# Extension.net
KiCad netlist of a schematic drawn in Altium Designer
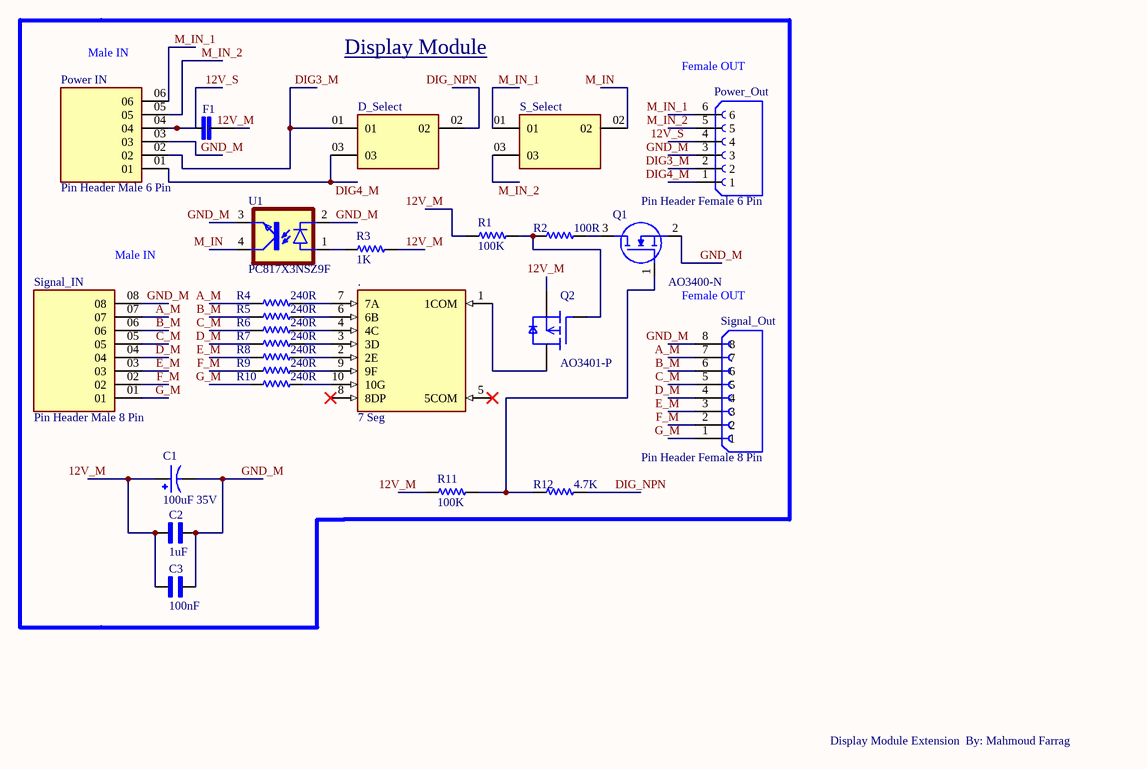
[diagram p0: Extension.SchDoc]

(export (version "E")
  (design (tool "Eeschema 10.0.6"))
  (components
    (comp (ref ".") (value "7 Seg") (footprint "2.3_7-SEG_DIS") (libsource (lib "Modules") (part "7 Seg")))
    (comp (ref "C1")
      (value "100uF 35V")
      (footprint "100uF 35V")
      (description "100ÂµF 35V Aluminum Electrolytic Capacitors Radial, Can - SMD 2000 Hrs @ 85Â°C")
      (fields (field (name "MP") "EEE-1VA101P") (field (name "MF") "Panasonic Electronic"))
      (libsource (lib "Capacitors") (part "100uF 35V"))
    )
    (comp (ref "C2")
      (value "1uF")
      (footprint "Capacitor 0805")
      (description "0.1 ÂµF Â±10% 50V Ceramic Capacitor X7R 0805 (2012 Metric)")
      (fields (field (name "MF") "Murata") (field (name "MP") "GCE21BR71H104KA01L"))
      (libsource (lib "Capacitors") (part "Capacitor 0805"))
    )
    (comp (ref "C3")
      (value "100nF")
      (footprint "Capacitor 0805")
      (description "0.1 ÂµF Â±10% 50V Ceramic Capacitor X7R 0805 (2012 Metric)")
      (fields (field (name "MF") "Murata") (field (name "MP") "GCE21BR71H104KA01L"))
      (libsource (lib "Capacitors") (part "Capacitor 0805"))
    )
    (comp (ref "D_Select")
      (value "Pin Header Male 3 Pin")
      (footprint "3Pin-M-Header_3MX1-254MM")
      (fields (field (name "MP") "TSW-101-23-L-T"))
      (libsource (lib "Connectors") (part "Pin Header Male 3 Pin"))
    )
    (comp (ref "F1")
      (value "Ferrite Bead 0805")
      (footprint "Ferrite Bead 0805")
      (description "BLM Series 0805 1 kOhm 200 mA 0.45 DCR Surface Mount Ferrite Bead")
      (fields (field (name "MF") "Murata") (field (name "MP") "BLM21AH102SN1D"))
      (libsource (lib "Resistors") (part "Ferrite Bead 0805"))
    )
    (comp (ref "Power IN")
      (value "Pin Header Male 6 Pin")
      (footprint "6Pin-M-Header_6MX1-254MM")
      (fields (field (name "MP") "MTSW-106-24-G-S-300"))
      (libsource (lib "Connectors") (part "Pin Header Male 6 Pin"))
    )
    (comp (ref "Power_Out")
      (value "Pin Header Female 6 Pin")
      (footprint "6Pin-F-Header_6FX1-254MM")
      (description "6 Position Total Single Row 2.54 mm Pitch Straight Female Header")
      (fields (field (name "MF") "Sullins Connector Solutions") (field (name "MP") "PPTC061LFBNRC"))
      (libsource (lib "Connectors") (part "Pin Header Female 6 Pin"))
    )
    (comp (ref "Q1")
      (value "AO3400-N")
      (footprint "AO-3400-N-SOT95")
      (description "N-Channel 30 V 5.8A (Ta) 1.4W (Ta) Surface Mount SOT-23-3")
      (fields (field (name "MF") "Alpha &") (field (name "MP") "AO3400"))
      (libsource (lib "ICs") (part "AO3400-N"))
    )
    (comp (ref "Q2")
      (value "AO3401-P")
      (footprint "AO-3401-P-SOT23-3")
      (description "P-Channel 30 V 4A (Ta) 1.4W (Ta) Surface Mount SOT-23-3")
      (fields (field (name "MF") "Alpha & Omega Semiconductor") (field (name "MP") "AO3401"))
      (libsource (lib "ICs") (part "AO3401-P"))
    )
    (comp (ref "R1")
      (value "100K")
      (footprint "Resistor 1206")
      (description "Fixed Resistor CRGCQ 1206 10K 5%")
      (fields (field (name "MF") "TE Connectivity") (field (name "MP") "CRGCQ1206J10K"))
      (libsource (lib "Resistors") (part "Resistor 1206"))
    )
    (comp (ref "R2")
      (value "100R")
      (footprint "Resistor 1206")
      (description "Fixed Resistor CRGCQ 1206 10K 5%")
      (fields (field (name "MF") "TE Connectivity") (field (name "MP") "CRGCQ1206J10K"))
      (libsource (lib "Resistors") (part "Resistor 1206"))
    )
    (comp (ref "R3")
      (value "1K")
      (footprint "Resistor 1206")
      (description "Fixed Resistor CRGCQ 1206 10K 5%")
      (fields (field (name "MF") "TE Connectivity") (field (name "MP") "CRGCQ1206J10K"))
      (libsource (lib "Resistors") (part "Resistor 1206"))
    )
    (comp (ref "R4")
      (value "240R")
      (footprint "Resistor 1206")
      (description "Fixed Resistor CRGCQ 1206 10K 5%")
      (fields (field (name "MF") "TE Connectivity") (field (name "MP") "CRGCQ1206J10K"))
      (libsource (lib "Resistors") (part "Resistor 1206"))
    )
    (comp (ref "R5")
      (value "240R")
      (footprint "Resistor 1206")
      (description "Fixed Resistor CRGCQ 1206 10K 5%")
      (fields (field (name "MF") "TE Connectivity") (field (name "MP") "CRGCQ1206J10K"))
      (libsource (lib "Resistors") (part "Resistor 1206"))
    )
    (comp (ref "R6")
      (value "240R")
      (footprint "Resistor 1206")
      (description "Fixed Resistor CRGCQ 1206 10K 5%")
      (fields (field (name "MF") "TE Connectivity") (field (name "MP") "CRGCQ1206J10K"))
      (libsource (lib "Resistors") (part "Resistor 1206"))
    )
    (comp (ref "R7")
      (value "240R")
      (footprint "Resistor 1206")
      (description "Fixed Resistor CRGCQ 1206 10K 5%")
      (fields (field (name "MF") "TE Connectivity") (field (name "MP") "CRGCQ1206J10K"))
      (libsource (lib "Resistors") (part "Resistor 1206"))
    )
    (comp (ref "R8")
      (value "240R")
      (footprint "Resistor 1206")
      (description "Fixed Resistor CRGCQ 1206 10K 5%")
      (fields (field (name "MF") "TE Connectivity") (field (name "MP") "CRGCQ1206J10K"))
      (libsource (lib "Resistors") (part "Resistor 1206"))
    )
    (comp (ref "R9")
      (value "240R")
      (footprint "Resistor 1206")
      (description "Fixed Resistor CRGCQ 1206 10K 5%")
      (fields (field (name "MF") "TE Connectivity") (field (name "MP") "CRGCQ1206J10K"))
      (libsource (lib "Resistors") (part "Resistor 1206"))
    )
    (comp (ref "R10")
      (value "240R")
      (footprint "Resistor 1206")
      (description "Fixed Resistor CRGCQ 1206 10K 5%")
      (fields (field (name "MF") "TE Connectivity") (field (name "MP") "CRGCQ1206J10K"))
      (libsource (lib "Resistors") (part "Resistor 1206"))
    )
    (comp (ref "R11")
      (value "100K")
      (footprint "Resistor 1206")
      (description "Fixed Resistor CRGCQ 1206 10K 5%")
      (fields (field (name "MF") "TE Connectivity") (field (name "MP") "CRGCQ1206J10K"))
      (libsource (lib "Resistors") (part "Resistor 1206"))
    )
    (comp (ref "R12")
      (value "4.7K")
      (footprint "Resistor 1206")
      (description "Fixed Resistor CRGCQ 1206 10K 5%")
      (fields (field (name "MF") "TE Connectivity") (field (name "MP") "CRGCQ1206J10K"))
      (libsource (lib "Resistors") (part "Resistor 1206"))
    )
    (comp (ref "Signal_IN")
      (value "Pin Header Male 8 Pin")
      (footprint "8Pin-M-Header_8MX1-254MM")
      (fields (field (name "MP") "HTSW-108-07-G-S-LL"))
      (libsource (lib "Connectors") (part "Pin Header Male 8 Pin"))
    )
    (comp (ref "Signal_Out")
      (value "Pin Header Female 8 Pin")
      (footprint "8Pin-F-Header_8FX1-254MM")
      (description "Headers & Wire Housings 2.54MM 0.1 8-PIN FEMALE HEADER")
      (fields (field (name "MP") "8Fx1-254mm") (field (name "MF") "Gravitech"))
      (libsource (lib "Connectors") (part "Pin Header Female 8 Pin"))
    )
    (comp (ref "S_Select")
      (value "Pin Header Male 3 Pin")
      (footprint "3Pin-M-Header_3MX1-254MM")
      (fields (field (name "MP") "TSW-101-23-L-T"))
      (libsource (lib "Connectors") (part "Pin Header Male 3 Pin"))
    )
    (comp (ref "U1")
      (value "PC817X3NSZ9F")
      (footprint "PC 817")
      (description "Optoisolator Transistor Output 5000Vrms 1 Channel 4-DIP")
      (fields (field (name "MF") "Sharp Microelectronics"))
      (libsource (lib "ICs") (part "PC817X3NSZ9F"))
    )
  )
  (nets
    (net (code "1") (name "/12V_M") (class "Default")
      (node (ref "C1") (pin "1") (pinfunction "1_1") (pintype "passive"))
      (node (ref "C2") (pin "1") (pinfunction "1_1") (pintype "passive"))
      (node (ref "C3") (pin "1") (pinfunction "1_1") (pintype "passive"))
      (node (ref "F1") (pin "2") (pinfunction "2_2") (pintype "passive"))
      (node (ref "Q2") (pin "2") (pinfunction "S_2") (pintype "passive"))
      (node (ref "R1") (pin "1") (pinfunction "1_1") (pintype "passive"))
      (node (ref "R11") (pin "1") (pinfunction "1_1") (pintype "passive"))
      (node (ref "R3") (pin "2") (pinfunction "2_2") (pintype "passive"))
    )
    (net (code "2") (name "/12V_S") (class "Default")
      (node (ref "F1") (pin "1") (pinfunction "1_1") (pintype "passive"))
      (node (ref "Power IN") (pin "04") (pinfunction "04_04") (pintype "passive"))
      (node (ref "Power_Out") (pin "4") (pinfunction "4_4") (pintype "passive"))
    )
    (net (code "3") (name "/A_M") (class "Default")
      (node (ref "R4") (pin "1") (pinfunction "1_1") (pintype "passive"))
      (node (ref "Signal_IN") (pin "07") (pinfunction "07_07") (pintype "passive"))
      (node (ref "Signal_Out") (pin "7") (pinfunction "7_7") (pintype "passive"))
    )
    (net (code "4") (name "/B_M") (class "Default")
      (node (ref "R5") (pin "1") (pinfunction "1_1") (pintype "passive"))
      (node (ref "Signal_IN") (pin "06") (pinfunction "06_06") (pintype "passive"))
      (node (ref "Signal_Out") (pin "6") (pinfunction "6_6") (pintype "passive"))
    )
    (net (code "5") (name "/C_M") (class "Default")
      (node (ref "R6") (pin "1") (pinfunction "1_1") (pintype "passive"))
      (node (ref "Signal_IN") (pin "05") (pinfunction "05_05") (pintype "passive"))
      (node (ref "Signal_Out") (pin "5") (pinfunction "5_5") (pintype "passive"))
    )
    (net (code "6") (name "/DIG3_M") (class "Default")
      (node (ref "D_Select") (pin "01") (pinfunction "01_01") (pintype "passive"))
      (node (ref "Power IN") (pin "02") (pinfunction "02_02") (pintype "passive"))
      (node (ref "Power_Out") (pin "2") (pinfunction "2_2") (pintype "passive"))
    )
    (net (code "7") (name "/DIG4_M") (class "Default")
      (node (ref "D_Select") (pin "03") (pinfunction "03_03") (pintype "passive"))
      (node (ref "Power IN") (pin "01") (pinfunction "01_01") (pintype "passive"))
      (node (ref "Power_Out") (pin "1") (pinfunction "1_1") (pintype "passive"))
    )
    (net (code "8") (name "/DIG_NPN") (class "Default")
      (node (ref "D_Select") (pin "02") (pinfunction "02_02") (pintype "passive"))
      (node (ref "R12") (pin "2") (pinfunction "2_2") (pintype "passive"))
    )
    (net (code "9") (name "/D_M") (class "Default")
      (node (ref "R7") (pin "1") (pinfunction "1_1") (pintype "passive"))
      (node (ref "Signal_IN") (pin "04") (pinfunction "04_04") (pintype "passive"))
      (node (ref "Signal_Out") (pin "4") (pinfunction "4_4") (pintype "passive"))
    )
    (net (code "10") (name "/E_M") (class "Default")
      (node (ref "R8") (pin "1") (pinfunction "1_1") (pintype "passive"))
      (node (ref "Signal_IN") (pin "03") (pinfunction "03_03") (pintype "passive"))
      (node (ref "Signal_Out") (pin "3") (pinfunction "3_3") (pintype "passive"))
    )
    (net (code "11") (name "/F_M") (class "Default")
      (node (ref "R9") (pin "1") (pinfunction "1_1") (pintype "passive"))
      (node (ref "Signal_IN") (pin "02") (pinfunction "02_02") (pintype "passive"))
      (node (ref "Signal_Out") (pin "2") (pinfunction "2_2") (pintype "passive"))
    )
    (net (code "12") (name "/GND_M") (class "Default")
      (node (ref "C1") (pin "2") (pinfunction "2_2") (pintype "passive"))
      (node (ref "C2") (pin "2") (pinfunction "2_2") (pintype "passive"))
      (node (ref "C3") (pin "2") (pinfunction "2_2") (pintype "passive"))
      (node (ref "Power IN") (pin "03") (pinfunction "03_03") (pintype "passive"))
      (node (ref "Power_Out") (pin "3") (pinfunction "3_3") (pintype "passive"))
      (node (ref "Q1") (pin "2") (pinfunction "S_2") (pintype "passive"))
      (node (ref "Signal_IN") (pin "08") (pinfunction "08_08") (pintype "passive"))
      (node (ref "Signal_Out") (pin "8") (pinfunction "8_8") (pintype "passive"))
      (node (ref "U1") (pin "2") (pinfunction "C_2") (pintype "passive"))
      (node (ref "U1") (pin "3") (pinfunction "EMIT_3") (pintype "passive"))
    )
    (net (code "13") (name "/G_M") (class "Default")
      (node (ref "R10") (pin "1") (pinfunction "1_1") (pintype "passive"))
      (node (ref "Signal_IN") (pin "01") (pinfunction "01_01") (pintype "passive"))
      (node (ref "Signal_Out") (pin "1") (pinfunction "1_1") (pintype "passive"))
    )
    (net (code "14") (name "/M_IN") (class "Default")
      (node (ref "S_Select") (pin "02") (pinfunction "02_02") (pintype "passive"))
      (node (ref "U1") (pin "4") (pinfunction "COL_4") (pintype "passive"))
    )
    (net (code "15") (name "/M_IN_1") (class "Default")
      (node (ref "Power IN") (pin "06") (pinfunction "06_06") (pintype "passive"))
      (node (ref "Power_Out") (pin "6") (pinfunction "6_6") (pintype "passive"))
      (node (ref "S_Select") (pin "01") (pinfunction "01_01") (pintype "passive"))
    )
    (net (code "16") (name "/M_IN_2") (class "Default")
      (node (ref "Power IN") (pin "05") (pinfunction "05_05") (pintype "passive"))
      (node (ref "Power_Out") (pin "5") (pinfunction "5_5") (pintype "passive"))
      (node (ref "S_Select") (pin "03") (pinfunction "03_03") (pintype "passive"))
    )
    (net (code "17") (name "Net-(.-1COM)") (class "Default")
      (node (ref ".") (pin "1") (pinfunction "1COM_1") (pintype "input"))
      (node (ref "Q2") (pin "3") (pinfunction "D_3") (pintype "passive"))
    )
    (net (code "18") (name "Net-(.-2E)") (class "Default")
      (node (ref ".") (pin "2") (pinfunction "2E_2") (pintype "input"))
      (node (ref "R8") (pin "2") (pinfunction "2_2") (pintype "passive"))
    )
    (net (code "19") (name "Net-(.-3D)") (class "Default")
      (node (ref ".") (pin "3") (pinfunction "3D_3") (pintype "input"))
      (node (ref "R7") (pin "2") (pinfunction "2_2") (pintype "passive"))
    )
    (net (code "20") (name "Net-(.-4C)") (class "Default")
      (node (ref ".") (pin "4") (pinfunction "4C_4") (pintype "input"))
      (node (ref "R6") (pin "2") (pinfunction "2_2") (pintype "passive"))
    )
    (net (code "21") (name "Net-(.-6B)") (class "Default")
      (node (ref ".") (pin "6") (pinfunction "6B_6") (pintype "input"))
      (node (ref "R5") (pin "2") (pinfunction "2_2") (pintype "passive"))
    )
    (net (code "22") (name "Net-(.-7A)") (class "Default")
      (node (ref ".") (pin "7") (pinfunction "7A_7") (pintype "input"))
      (node (ref "R4") (pin "2") (pinfunction "2_2") (pintype "passive"))
    )
    (net (code "23") (name "Net-(.-9F)") (class "Default")
      (node (ref ".") (pin "9") (pinfunction "9F_9") (pintype "input"))
      (node (ref "R9") (pin "2") (pinfunction "2_2") (pintype "passive"))
    )
    (net (code "24") (name "Net-(.-10G)") (class "Default")
      (node (ref ".") (pin "10") (pinfunction "10G_10") (pintype "input"))
      (node (ref "R10") (pin "2") (pinfunction "2_2") (pintype "passive"))
    )
    (net (code "25") (name "Net-(Q1-D)") (class "Default")
      (node (ref "Q1") (pin "3") (pinfunction "D_3") (pintype "passive"))
      (node (ref "R2") (pin "2") (pinfunction "2_2") (pintype "passive"))
    )
    (net (code "26") (name "Net-(Q1-G)") (class "Default")
      (node (ref "Q1") (pin "1") (pinfunction "G_1") (pintype "passive"))
      (node (ref "R11") (pin "2") (pinfunction "2_2") (pintype "passive"))
      (node (ref "R12") (pin "1") (pinfunction "1_1") (pintype "passive"))
    )
    (net (code "27") (name "Net-(Q2-G)") (class "Default")
      (node (ref "Q2") (pin "1") (pinfunction "G_1") (pintype "passive"))
      (node (ref "R1") (pin "2") (pinfunction "2_2") (pintype "passive"))
      (node (ref "R2") (pin "1") (pinfunction "1_1") (pintype "passive"))
    )
    (net (code "28") (name "Net-(U1-A)") (class "Default")
      (node (ref "R3") (pin "1") (pinfunction "1_1") (pintype "passive"))
      (node (ref "U1") (pin "1") (pinfunction "A_1") (pintype "passive"))
    )
    (net (code "29") (name "unconnected-(.-5COM-Pad5)") (class "Default")
      (node (ref ".") (pin "5") (pinfunction "5COM_5") (pintype "input+no_connect"))
    )
    (net (code "30") (name "unconnected-(.-8DP-Pad8)") (class "Default")
      (node (ref ".") (pin "8") (pinfunction "8DP_8") (pintype "input+no_connect"))
    )
  )
)
